# FULLBOARD_Rough_Draft.net
KiCad netlist of a schematic drawn in EAGLE
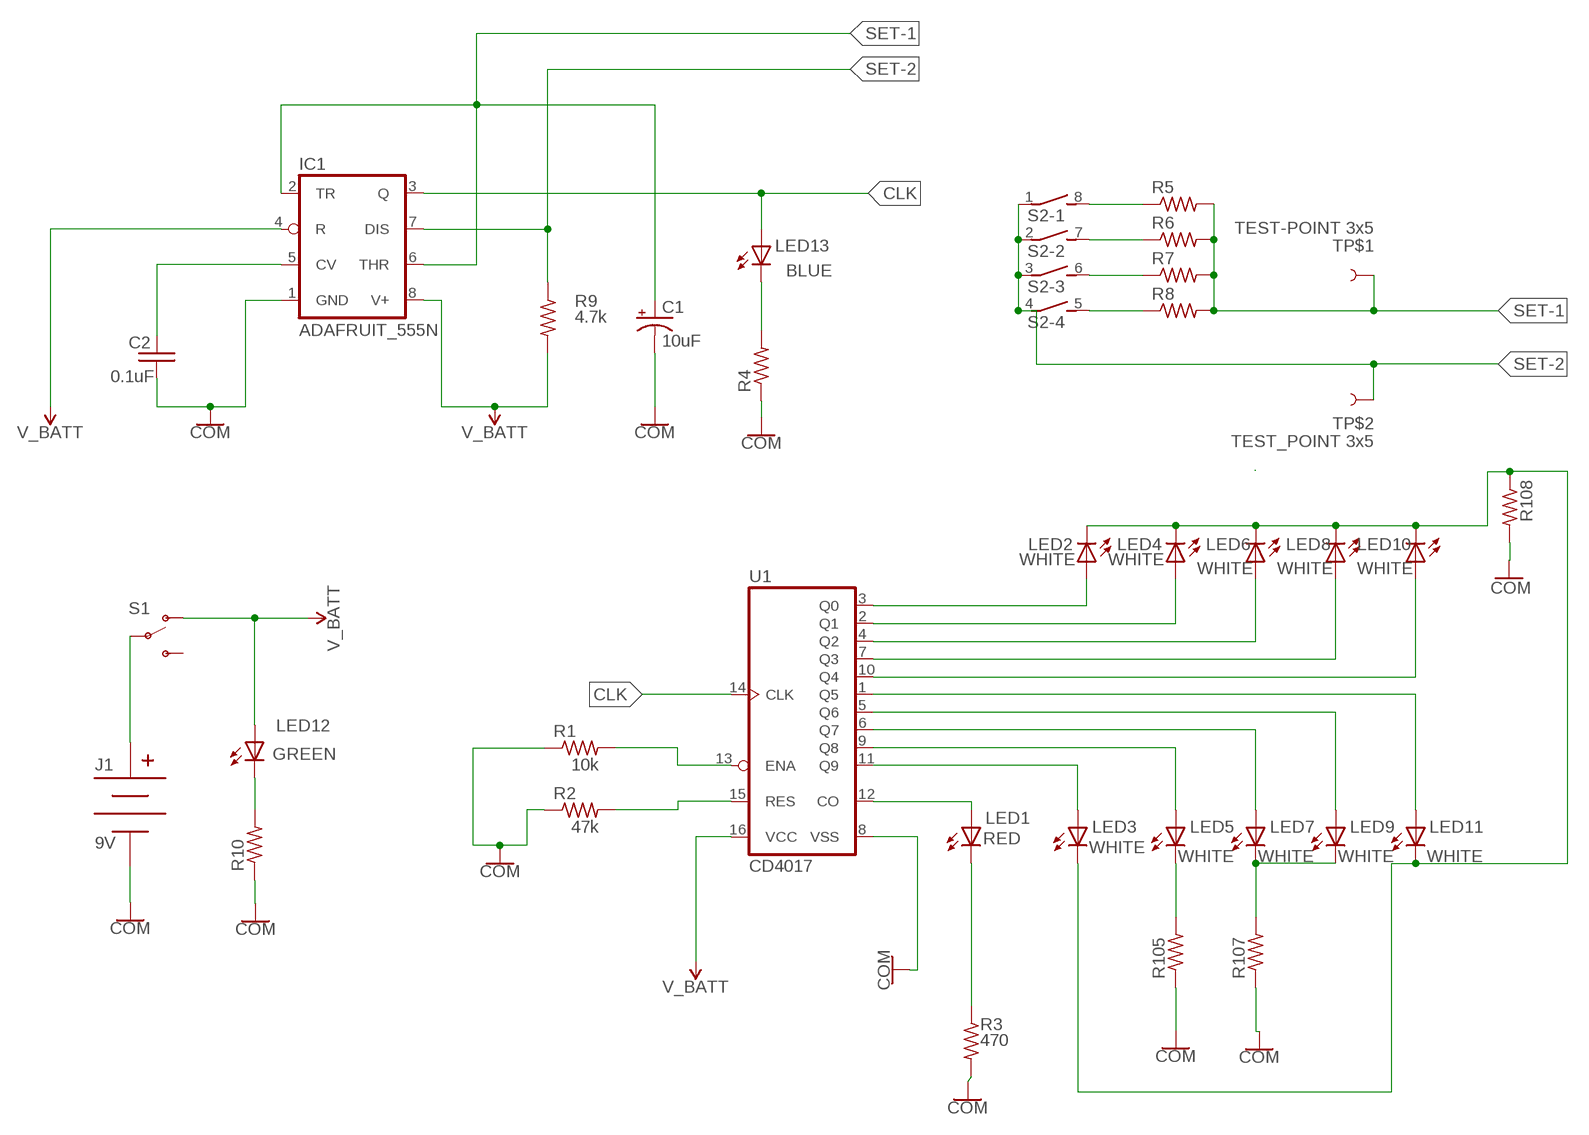
[diagram p0: schematic, sheet 1]

(export (version "E")
  (design (tool "Eeschema 10.0.6"))
  (components
    (comp (ref "C1")
      (value "10uF")
      (footprint "eagle-import:ADAFRUIT_E2-5")
      (libsource (lib "eagle-import") (part "ADAFRUIT_CPOL-USE2-5"))
    )
    (comp (ref "C2")
      (value "0.1uF")
      (footprint "eagle-import:ADAFRUIT_C025-025X050")
      (libsource (lib "eagle-import") (part "ADAFRUIT_C-US025-025X050"))
    )
    (comp (ref "IC1")
      (value "ADAFRUIT_555N")
      (footprint "eagle-import:ADAFRUIT_DIL08-ROUND")
      (libsource (lib "eagle-import") (part "ADAFRUIT_555N"))
    )
    (comp (ref "J1")
      (value "9V")
      (footprint "eagle-import:SPARKFUN-CONNECTORS_BC9VPC")
      (libsource (lib "eagle-import") (part "SPARKFUN-CONNECTORS_BC9VPC"))
    )
    (comp (ref "LED1")
      (value "RED")
      (footprint "eagle-import:ADAFRUIT_LED5MM")
      (libsource (lib "eagle-import") (part "SECTION C_ADAFRUIT_LED5MM"))
    )
    (comp (ref "LED2")
      (value "WHITE")
      (footprint "eagle-import:ADAFRUIT_LED5MM")
      (libsource (lib "eagle-import") (part "SECTION C_ADAFRUIT_LED5MM"))
    )
    (comp (ref "LED3")
      (value "WHITE")
      (footprint "eagle-import:ADAFRUIT_LED5MM")
      (libsource (lib "eagle-import") (part "SECTION C_ADAFRUIT_LED5MM"))
    )
    (comp (ref "LED4")
      (value "WHITE")
      (footprint "eagle-import:ADAFRUIT_LED5MM")
      (libsource (lib "eagle-import") (part "SECTION C_ADAFRUIT_LED5MM"))
    )
    (comp (ref "LED5")
      (value "WHITE")
      (footprint "eagle-import:ADAFRUIT_LED5MM")
      (libsource (lib "eagle-import") (part "SECTION C_ADAFRUIT_LED5MM"))
    )
    (comp (ref "LED6")
      (value "WHITE")
      (footprint "eagle-import:ADAFRUIT_LED5MM")
      (libsource (lib "eagle-import") (part "SECTION C_ADAFRUIT_LED5MM"))
    )
    (comp (ref "LED7")
      (value "WHITE")
      (footprint "eagle-import:ADAFRUIT_LED5MM")
      (libsource (lib "eagle-import") (part "SECTION C_ADAFRUIT_LED5MM"))
    )
    (comp (ref "LED8")
      (value "WHITE")
      (footprint "eagle-import:ADAFRUIT_LED5MM")
      (libsource (lib "eagle-import") (part "SECTION C_ADAFRUIT_LED5MM"))
    )
    (comp (ref "LED9")
      (value "WHITE")
      (footprint "eagle-import:ADAFRUIT_LED5MM")
      (libsource (lib "eagle-import") (part "SECTION C_ADAFRUIT_LED5MM"))
    )
    (comp (ref "LED10")
      (value "WHITE")
      (footprint "eagle-import:ADAFRUIT_LED5MM")
      (libsource (lib "eagle-import") (part "SECTION C_ADAFRUIT_LED5MM"))
    )
    (comp (ref "LED11")
      (value "WHITE")
      (footprint "eagle-import:ADAFRUIT_LED5MM")
      (libsource (lib "eagle-import") (part "SECTION C_ADAFRUIT_LED5MM"))
    )
    (comp (ref "LED12")
      (value "ADAFRUIT_LED5MM")
      (footprint "eagle-import:ADAFRUIT_LED5MM")
      (fields (field (name "COLOR") "GREEN"))
      (libsource (lib "eagle-import") (part "ADAFRUIT_LED5MM"))
    )
    (comp (ref "LED13")
      (value "ADAFRUIT_LED5MM")
      (footprint "eagle-import:ADAFRUIT_LED5MM")
      (fields (field (name "COLOR") "BLUE"))
      (libsource (lib "eagle-import") (part "SECTION B_ADAFRUIT_LED5MM"))
    )
    (comp (ref "R1")
      (value "10k")
      (footprint "eagle-import:ADAFRUIT_0207_10")
      (libsource (lib "eagle-import") (part "SECTION C_ADAFRUIT_R-US_0207/10"))
    )
    (comp (ref "R2")
      (value "47k")
      (footprint "eagle-import:ADAFRUIT_0207_10")
      (libsource (lib "eagle-import") (part "SECTION C_ADAFRUIT_R-US_0207/10"))
    )
    (comp (ref "R3")
      (value "470")
      (footprint "eagle-import:ADAFRUIT_0207_10")
      (libsource (lib "eagle-import") (part "SECTION C_ADAFRUIT_R-US_0207/10"))
    )
    (comp (ref "R4")
      (value "ADAFRUIT_R-US_0207/10")
      (footprint "eagle-import:ADAFRUIT_0207_10")
      (libsource (lib "eagle-import") (part "SECTION C_ADAFRUIT_R-US_0207/10"))
    )
    (comp (ref "R5")
      (value "ADAFRUIT_R-US_0207/10")
      (footprint "eagle-import:ADAFRUIT_0207_10")
      (libsource (lib "eagle-import") (part "ADAFRUIT_R-US_0207/10"))
    )
    (comp (ref "R6")
      (value "ADAFRUIT_R-US_0207/10")
      (footprint "eagle-import:ADAFRUIT_0207_10")
      (libsource (lib "eagle-import") (part "ADAFRUIT_R-US_0207/10"))
    )
    (comp (ref "R7")
      (value "ADAFRUIT_R-US_0207/10")
      (footprint "eagle-import:ADAFRUIT_0207_10")
      (libsource (lib "eagle-import") (part "ADAFRUIT_R-US_0207/10"))
    )
    (comp (ref "R8")
      (value "ADAFRUIT_R-US_0207/10")
      (footprint "eagle-import:ADAFRUIT_0207_10")
      (libsource (lib "eagle-import") (part "ADAFRUIT_R-US_0207/10"))
    )
    (comp (ref "R9")
      (value "4.7k")
      (footprint "eagle-import:ADAFRUIT_0207_10")
      (libsource (lib "eagle-import") (part "SECTION B_ADAFRUIT_R-US_0207/10"))
    )
    (comp (ref "R10")
      (value "ADAFRUIT_R-US_0207/10")
      (footprint "eagle-import:ADAFRUIT_0207_10")
      (libsource (lib "eagle-import") (part "SECTION C_ADAFRUIT_R-US_0207/10"))
    )
    (comp (ref "R105")
      (value "ADAFRUIT_R-US_0207/10")
      (footprint "eagle-import:ADAFRUIT_0207_10")
      (libsource (lib "eagle-import") (part "SECTION C_ADAFRUIT_R-US_0207/10"))
    )
    (comp (ref "R107")
      (value "ADAFRUIT_R-US_0207/10")
      (footprint "eagle-import:ADAFRUIT_0207_10")
      (libsource (lib "eagle-import") (part "SECTION C_ADAFRUIT_R-US_0207/10"))
    )
    (comp (ref "R108")
      (value "ADAFRUIT_R-US_0207/10")
      (footprint "eagle-import:ADAFRUIT_0207_10")
      (libsource (lib "eagle-import") (part "SECTION C_ADAFRUIT_R-US_0207/10"))
    )
    (comp (ref "S1")
      (value "SPARKFUN-SWITCHES_SWITCH-SPDT-PTH-11.6X4.0MM")
      (footprint "eagle-import:SPARKFUN-SWITCHES_SWITCH_SPDT_PTH_11.6X4.0MM")
      (libsource (lib "eagle-import") (part "SPARKFUN-SWITCHES_SWITCH-SPDT-PTH-11.6X4.0MM"))
    )
    (comp (ref "S2")
      (value "SWITCH-DIL_DIP04S")
      (footprint "eagle-import:SWITCH-DIL_DIP04S")
      (libsource (lib "eagle-import") (part "SWITCH-DIL_DIP04S"))
    )
    (comp (ref "TP$1")
      (value "TEST-POINT 3x5")
      (footprint "eagle-import:SPARKFUN-CONNECTORS_PAD.03X.05")
      (libsource (lib "eagle-import") (part "SPARKFUN-CONNECTORS_TEST-POINT3X5"))
    )
    (comp (ref "TP$2")
      (value "TEST_POINT 3x5")
      (footprint "eagle-import:SPARKFUN-CONNECTORS_PAD.03X.05")
      (libsource (lib "eagle-import") (part "SPARKFUN-CONNECTORS_TEST-POINT3X5"))
    )
    (comp (ref "U1")
      (value "CD4017")
      (footprint "eagle-import:SPARKFUN-IC-LOGIC_DIP16")
      (libsource (lib "eagle-import") (part "SPARKFUN-IC-LOGIC_CD4017"))
    )
  )
  (nets
    (net (code "1") (name "CLK") (class "Default")
      (node (ref "IC1") (pin "3") (pinfunction "Q_3") (pintype "output"))
      (node (ref "LED13") (pin "A") (pinfunction "A_A") (pintype "passive"))
      (node (ref "U1") (pin "14") (pinfunction "CLK_14") (pintype "input"))
    )
    (net (code "2") (name "COM") (class "Default")
      (node (ref "C1") (pin "-") (pinfunction "-_-") (pintype "passive"))
      (node (ref "C2") (pin "2") (pinfunction "2_2") (pintype "passive"))
      (node (ref "IC1") (pin "1") (pinfunction "GND_1") (pintype "power_in"))
      (node (ref "J1") (pin "V-") (pinfunction "V-_V-") (pintype "bidirectional"))
      (node (ref "R1") (pin "1") (pinfunction "1_1") (pintype "passive"))
      (node (ref "R10") (pin "1") (pinfunction "1_1") (pintype "passive"))
      (node (ref "R105") (pin "1") (pinfunction "1_1") (pintype "passive"))
      (node (ref "R107") (pin "1") (pinfunction "1_1") (pintype "passive"))
      (node (ref "R108") (pin "2") (pinfunction "2_2") (pintype "passive"))
      (node (ref "R2") (pin "1") (pinfunction "1_1") (pintype "passive"))
      (node (ref "R3") (pin "2") (pinfunction "2_2") (pintype "passive"))
      (node (ref "R4") (pin "1") (pinfunction "1_1") (pintype "passive"))
      (node (ref "U1") (pin "8") (pinfunction "VSS_8") (pintype "bidirectional"))
    )
    (net (code "3") (name "Net-(IC1-CV)") (class "Default")
      (node (ref "C2") (pin "1") (pinfunction "1_1") (pintype "passive"))
      (node (ref "IC1") (pin "5") (pinfunction "CV_5") (pintype "input"))
    )
    (net (code "4") (name "Net-(LED1-C)") (class "Default")
      (node (ref "LED1") (pin "K") (pinfunction "C_K") (pintype "passive"))
      (node (ref "R3") (pin "1") (pinfunction "1_1") (pintype "passive"))
    )
    (net (code "5") (name "Net-(LED5-C)") (class "Default")
      (node (ref "LED5") (pin "K") (pinfunction "C_K") (pintype "passive"))
      (node (ref "R105") (pin "2") (pinfunction "2_2") (pintype "passive"))
    )
    (net (code "6") (name "Net-(LED7-C)") (class "Default")
      (node (ref "LED7") (pin "K") (pinfunction "C_K") (pintype "passive"))
      (node (ref "LED9") (pin "K") (pinfunction "C_K") (pintype "passive"))
      (node (ref "R107") (pin "2") (pinfunction "2_2") (pintype "passive"))
    )
    (net (code "7") (name "Net-(LED10-C)") (class "Default")
      (node (ref "LED10") (pin "K") (pinfunction "C_K") (pintype "passive"))
      (node (ref "LED11") (pin "K") (pinfunction "C_K") (pintype "passive"))
      (node (ref "LED2") (pin "K") (pinfunction "C_K") (pintype "passive"))
      (node (ref "LED3") (pin "K") (pinfunction "C_K") (pintype "passive"))
      (node (ref "LED4") (pin "K") (pinfunction "C_K") (pintype "passive"))
      (node (ref "LED6") (pin "K") (pinfunction "C_K") (pintype "passive"))
      (node (ref "LED8") (pin "K") (pinfunction "C_K") (pintype "passive"))
      (node (ref "R108") (pin "1") (pinfunction "1_1") (pintype "passive"))
    )
    (net (code "8") (name "Net-(LED12-C)") (class "Default")
      (node (ref "LED12") (pin "K") (pinfunction "C_K") (pintype "passive"))
      (node (ref "R10") (pin "2") (pinfunction "2_2") (pintype "passive"))
    )
    (net (code "9") (name "Net-(LED13-C)") (class "Default")
      (node (ref "LED13") (pin "K") (pinfunction "C_K") (pintype "passive"))
      (node (ref "R4") (pin "2") (pinfunction "2_2") (pintype "passive"))
    )
    (net (code "10") (name "Net-(S1-P)") (class "Default")
      (node (ref "J1") (pin "V+") (pinfunction "V+_V+") (pintype "bidirectional"))
      (node (ref "S1") (pin "2") (pinfunction "P_2") (pintype "passive"))
    )
    (net (code "11") (name "Net-(S2A-2)") (class "Default")
      (node (ref "R5") (pin "1") (pinfunction "1_1") (pintype "passive"))
      (node (ref "S2") (pin "8") (pinfunction "2_8") (pintype "passive"))
    )
    (net (code "12") (name "Net-(S2B-2)") (class "Default")
      (node (ref "R6") (pin "1") (pinfunction "1_1") (pintype "passive"))
      (node (ref "S2") (pin "7") (pinfunction "2_7") (pintype "passive"))
    )
    (net (code "13") (name "Net-(S2C-2)") (class "Default")
      (node (ref "R7") (pin "1") (pinfunction "1_1") (pintype "passive"))
      (node (ref "S2") (pin "6") (pinfunction "2_6") (pintype "passive"))
    )
    (net (code "14") (name "Net-(S2D-2)") (class "Default")
      (node (ref "R8") (pin "1") (pinfunction "1_1") (pintype "passive"))
      (node (ref "S2") (pin "5") (pinfunction "2_5") (pintype "passive"))
    )
    (net (code "15") (name "Net-(U1-CO)") (class "Default")
      (node (ref "LED1") (pin "A") (pinfunction "A_A") (pintype "passive"))
      (node (ref "U1") (pin "12") (pinfunction "CO_12") (pintype "output"))
    )
    (net (code "16") (name "Net-(U1-ENA)") (class "Default")
      (node (ref "R1") (pin "2") (pinfunction "2_2") (pintype "passive"))
      (node (ref "U1") (pin "13") (pinfunction "ENA_13") (pintype "input"))
    )
    (net (code "17") (name "Net-(U1-Q0)") (class "Default")
      (node (ref "LED2") (pin "A") (pinfunction "A_A") (pintype "passive"))
      (node (ref "U1") (pin "3") (pinfunction "Q0_3") (pintype "output"))
    )
    (net (code "18") (name "Net-(U1-Q1)") (class "Default")
      (node (ref "LED4") (pin "A") (pinfunction "A_A") (pintype "passive"))
      (node (ref "U1") (pin "2") (pinfunction "Q1_2") (pintype "output"))
    )
    (net (code "19") (name "Net-(U1-Q2)") (class "Default")
      (node (ref "LED6") (pin "A") (pinfunction "A_A") (pintype "passive"))
      (node (ref "U1") (pin "4") (pinfunction "Q2_4") (pintype "output"))
    )
    (net (code "20") (name "Net-(U1-Q3)") (class "Default")
      (node (ref "LED8") (pin "A") (pinfunction "A_A") (pintype "passive"))
      (node (ref "U1") (pin "7") (pinfunction "Q3_7") (pintype "output"))
    )
    (net (code "21") (name "Net-(U1-Q4)") (class "Default")
      (node (ref "LED10") (pin "A") (pinfunction "A_A") (pintype "passive"))
      (node (ref "U1") (pin "10") (pinfunction "Q4_10") (pintype "output"))
    )
    (net (code "22") (name "Net-(U1-Q5)") (class "Default")
      (node (ref "LED11") (pin "A") (pinfunction "A_A") (pintype "passive"))
      (node (ref "U1") (pin "1") (pinfunction "Q5_1") (pintype "output"))
    )
    (net (code "23") (name "Net-(U1-Q6)") (class "Default")
      (node (ref "LED9") (pin "A") (pinfunction "A_A") (pintype "passive"))
      (node (ref "U1") (pin "5") (pinfunction "Q6_5") (pintype "output"))
    )
    (net (code "24") (name "Net-(U1-Q7)") (class "Default")
      (node (ref "LED7") (pin "A") (pinfunction "A_A") (pintype "passive"))
      (node (ref "U1") (pin "6") (pinfunction "Q7_6") (pintype "output"))
    )
    (net (code "25") (name "Net-(U1-Q8)") (class "Default")
      (node (ref "LED5") (pin "A") (pinfunction "A_A") (pintype "passive"))
      (node (ref "U1") (pin "9") (pinfunction "Q8_9") (pintype "output"))
    )
    (net (code "26") (name "Net-(U1-Q9)") (class "Default")
      (node (ref "LED3") (pin "A") (pinfunction "A_A") (pintype "passive"))
      (node (ref "U1") (pin "11") (pinfunction "Q9_11") (pintype "output"))
    )
    (net (code "27") (name "Net-(U1-RES)") (class "Default")
      (node (ref "R2") (pin "2") (pinfunction "2_2") (pintype "passive"))
      (node (ref "U1") (pin "15") (pinfunction "RES_15") (pintype "input"))
    )
    (net (code "28") (name "SET-1") (class "Default")
      (node (ref "C1") (pin "+") (pinfunction "+_+") (pintype "passive"))
      (node (ref "IC1") (pin "2") (pinfunction "TR_2") (pintype "input"))
      (node (ref "IC1") (pin "6") (pinfunction "THR_6") (pintype "input"))
      (node (ref "R5") (pin "2") (pinfunction "2_2") (pintype "passive"))
      (node (ref "R6") (pin "2") (pinfunction "2_2") (pintype "passive"))
      (node (ref "R7") (pin "2") (pinfunction "2_2") (pintype "passive"))
      (node (ref "R8") (pin "2") (pinfunction "2_2") (pintype "passive"))
      (node (ref "TP$1") (pin "P$1") (pinfunction "1_P$1") (pintype "bidirectional"))
    )
    (net (code "29") (name "SET-2") (class "Default")
      (node (ref "IC1") (pin "7") (pinfunction "DIS_7") (pintype "input"))
      (node (ref "R9") (pin "1") (pinfunction "1_1") (pintype "passive"))
      (node (ref "S2") (pin "1") (pinfunction "1_1") (pintype "passive"))
      (node (ref "S2") (pin "2") (pinfunction "1_2") (pintype "passive"))
      (node (ref "S2") (pin "3") (pinfunction "1_3") (pintype "passive"))
      (node (ref "S2") (pin "4") (pinfunction "1_4") (pintype "passive"))
      (node (ref "TP$2") (pin "P$1") (pinfunction "1_P$1") (pintype "bidirectional"))
    )
    (net (code "30") (name "V_BATT") (class "Default")
      (node (ref "IC1") (pin "4") (pinfunction "R_4") (pintype "input"))
      (node (ref "IC1") (pin "8") (pinfunction "V+_8") (pintype "power_in"))
      (node (ref "LED12") (pin "A") (pinfunction "A_A") (pintype "passive"))
      (node (ref "R9") (pin "2") (pinfunction "2_2") (pintype "passive"))
      (node (ref "S1") (pin "1") (pinfunction "O_1") (pintype "passive"))
      (node (ref "U1") (pin "16") (pinfunction "VCC_16") (pintype "bidirectional"))
    )
    (net (code "31") (name "unconnected-(S1-S-Pad3)") (class "Default")
      (node (ref "S1") (pin "3") (pinfunction "S_3") (pintype "passive"))
    )
  )
)
